# PowerSupply.net
KiCad netlist of a schematic drawn in Altium Designer
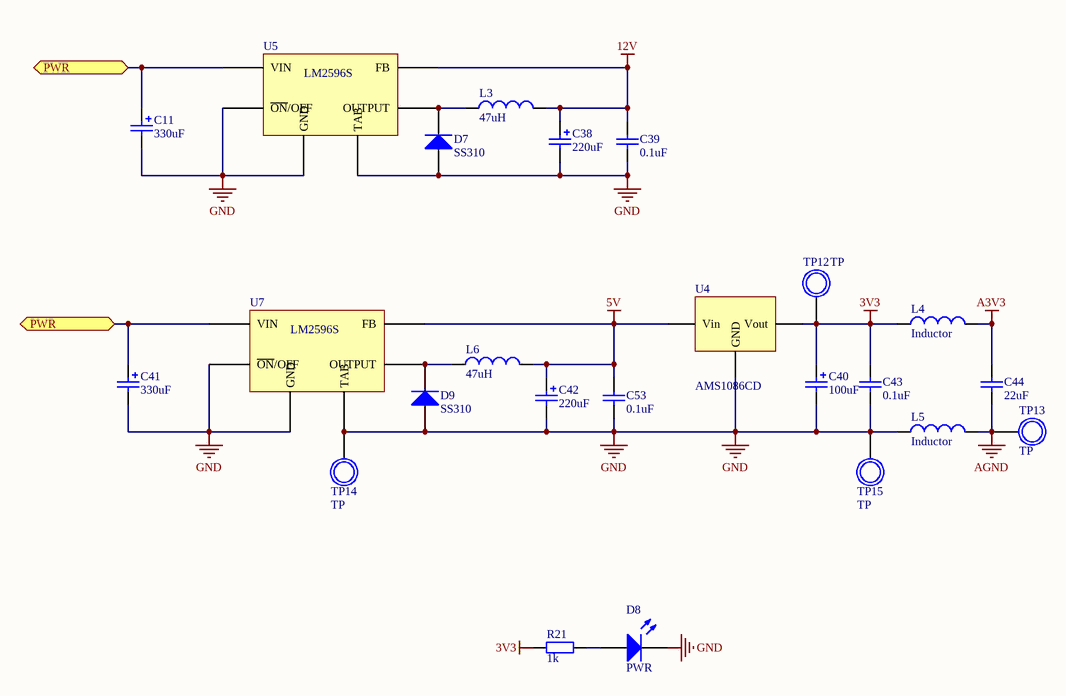
[diagram p0: PowerSupply.SchDoc]

(export (version "E")
  (design (tool "Eeschema 10.0.6"))
  (components
    (comp (ref "C11")
      (value "330uF")
      (footprint "CAPAE109103X105N")
      (description "cap pol")
      (fields (field (name "TOLERANCE") "~{+}- 10%"))
      (libsource (lib "PCB_Project") (part "CAP_Pol"))
    )
    (comp (ref "C38")
      (value "220uF")
      (footprint "CAPAE109103X105N")
      (description "cap pol")
      (fields (field (name "TOLERANCE") "~{+}- 10%"))
      (libsource (lib "PCB_Project") (part "CAP_Pol"))
    )
    (comp (ref "C39")
      (value "0.1uF")
      (footprint "CAP1206")
      (description "CAP NON-POL")
      (fields (field (name "TOLERANCE") "+/-10%"))
      (libsource (lib "PCB_Project") (part "CAP"))
    )
    (comp (ref "C40")
      (value "100uF")
      (footprint "CAPAE109103X105N")
      (description "cap pol")
      (fields (field (name "TOLERANCE") "~{+}- 10%"))
      (libsource (lib "PCB_Project") (part "CAP_Pol"))
    )
    (comp (ref "C41")
      (value "330uF")
      (footprint "CAPAE109103X105N")
      (description "cap pol")
      (fields (field (name "TOLERANCE") "~{+}- 10%"))
      (libsource (lib "PCB_Project") (part "CAP_Pol"))
    )
    (comp (ref "C42")
      (value "220uF")
      (footprint "CAPAE109103X105N")
      (description "cap pol")
      (fields (field (name "TOLERANCE") "~{+}- 10%"))
      (libsource (lib "PCB_Project") (part "CAP_Pol"))
    )
    (comp (ref "C43")
      (value "0.1uF")
      (footprint "CAP0603")
      (description "CAP NON-POL")
      (fields (field (name "TOLERANCE") "+/-10%"))
      (libsource (lib "PCB_Project") (part "CAP"))
    )
    (comp (ref "C44")
      (value "22uF")
      (footprint "CAP1206")
      (description "CAP NON-POL")
      (fields (field (name "TOLERANCE") "+/-10%"))
      (libsource (lib "PCB_Project") (part "CAP"))
    )
    (comp (ref "C53")
      (value "0.1uF")
      (footprint "CAP1206")
      (description "CAP NON-POL")
      (fields (field (name "TOLERANCE") "+/-10%"))
      (libsource (lib "PCB_Project") (part "CAP"))
    )
    (comp (ref "D7")
      (value "SS310")
      (footprint "SMA")
      (description "diode")
      (libsource (lib "PCB_Project") (part "Diode"))
    )
    (comp (ref "D8")
      (value "PWR")
      (footprint "LED0603")
      (description "led")
      (libsource (lib "PCB_Project") (part "LED"))
    )
    (comp (ref "D9")
      (value "SS310")
      (footprint "SMA")
      (description "diode")
      (libsource (lib "PCB_Project") (part "Diode"))
    )
    (comp (ref "L3")
      (value "47uH")
      (footprint "CDRH125")
      (description "Inductor")
      (libsource (lib "PCB_Project") (part "Inductor"))
    )
    (comp (ref "L4")
      (value "Inductor")
      (footprint "IND1206")
      (libsource (lib "PCB_Project") (part "Inductor"))
    )
    (comp (ref "L5")
      (value "Inductor")
      (footprint "IND1206")
      (libsource (lib "PCB_Project") (part "Inductor"))
    )
    (comp (ref "L6")
      (value "47uH")
      (footprint "CDRH125")
      (description "Inductor")
      (libsource (lib "PCB_Project") (part "Inductor"))
    )
    (comp (ref "R21")
      (value "1k")
      (footprint "RES0603")
      (description "res")
      (libsource (lib "PCB_Project") (part "RES"))
    )
    (comp (ref "TP12")
      (value "TP")
      (footprint "PAD85R")
      (description "test point")
      (libsource (lib "PCB_Project") (part "Test_Point"))
    )
    (comp (ref "TP13")
      (value "TP")
      (footprint "PAD85R")
      (description "test point")
      (libsource (lib "PCB_Project") (part "Test_Point"))
    )
    (comp (ref "TP14")
      (value "TP")
      (footprint "PAD85R")
      (description "test point")
      (libsource (lib "PCB_Project") (part "Test_Point"))
    )
    (comp (ref "TP15")
      (value "TP")
      (footprint "PAD85R")
      (description "test point")
      (libsource (lib "PCB_Project") (part "Test_Point"))
    )
    (comp (ref "U4")
      (value "AMS1086CD")
      (footprint "DPAK228P1003X238-3N")
      (description "LDO")
      (libsource (lib "PCB_Project") (part "AMS1086CD"))
    )
    (comp (ref "U5")
      (value "LM2596S")
      (footprint "DPAK170P1435X465-6N")
      (description "1A,52KHz,Step-Down")
      (libsource (lib "PCB_Project") (part "LM2596S"))
    )
    (comp (ref "U7")
      (value "LM2596S")
      (footprint "DPAK170P1435X465-6N")
      (description "1A,52KHz,Step-Down")
      (libsource (lib "PCB_Project") (part "LM2596S"))
    )
  )
  (nets
    (net (code "1") (name "/PWR") (class "Default")
      (node (ref "C11") (pin "2") (pinfunction "2_2") (pintype "passive"))
      (node (ref "C41") (pin "2") (pinfunction "2_2") (pintype "passive"))
      (node (ref "U5") (pin "1") (pinfunction "VIN_1") (pintype "passive"))
      (node (ref "U7") (pin "1") (pinfunction "VIN_1") (pintype "passive"))
    )
    (net (code "2") (name "3V3") (class "Default")
      (node (ref "C40") (pin "2") (pinfunction "2_2") (pintype "passive"))
      (node (ref "C43") (pin "1") (pinfunction "1_1") (pintype "passive"))
      (node (ref "L4") (pin "1") (pinfunction "1_1") (pintype "passive"))
      (node (ref "R21") (pin "1") (pinfunction "1_1") (pintype "passive"))
      (node (ref "TP12") (pin "1") (pinfunction "1_1") (pintype "passive"))
      (node (ref "U4") (pin "2") (pinfunction "Vout_2") (pintype "passive"))
    )
    (net (code "3") (name "5V") (class "Default")
      (node (ref "C42") (pin "2") (pinfunction "2_2") (pintype "passive"))
      (node (ref "C53") (pin "1") (pinfunction "1_1") (pintype "passive"))
      (node (ref "L6") (pin "2") (pinfunction "2_2") (pintype "passive"))
      (node (ref "U4") (pin "3") (pinfunction "Vin_3") (pintype "passive"))
      (node (ref "U7") (pin "4") (pinfunction "FB_4") (pintype "passive"))
    )
    (net (code "4") (name "12V") (class "Default")
      (node (ref "C38") (pin "2") (pinfunction "2_2") (pintype "passive"))
      (node (ref "C39") (pin "1") (pinfunction "1_1") (pintype "passive"))
      (node (ref "L3") (pin "2") (pinfunction "2_2") (pintype "passive"))
      (node (ref "U5") (pin "4") (pinfunction "FB_4") (pintype "passive"))
    )
    (net (code "5") (name "A3V3") (class "Default")
      (node (ref "C44") (pin "1") (pinfunction "1_1") (pintype "passive"))
      (node (ref "L4") (pin "2") (pinfunction "2_2") (pintype "passive"))
    )
    (net (code "6") (name "AGND") (class "Default")
      (node (ref "C44") (pin "2") (pinfunction "2_2") (pintype "passive"))
      (node (ref "L5") (pin "2") (pinfunction "2_2") (pintype "passive"))
      (node (ref "TP13") (pin "1") (pinfunction "1_1") (pintype "passive"))
    )
    (net (code "7") (name "GND") (class "Default")
      (node (ref "C11") (pin "1") (pinfunction "1_1") (pintype "passive"))
      (node (ref "C38") (pin "1") (pinfunction "1_1") (pintype "passive"))
      (node (ref "C39") (pin "2") (pinfunction "2_2") (pintype "passive"))
      (node (ref "C40") (pin "1") (pinfunction "1_1") (pintype "passive"))
      (node (ref "C41") (pin "1") (pinfunction "1_1") (pintype "passive"))
      (node (ref "C42") (pin "1") (pinfunction "1_1") (pintype "passive"))
      (node (ref "C43") (pin "2") (pinfunction "2_2") (pintype "passive"))
      (node (ref "C53") (pin "2") (pinfunction "2_2") (pintype "passive"))
      (node (ref "D7") (pin "1") (pinfunction "A_1") (pintype "passive"))
      (node (ref "D8") (pin "2") (pinfunction "K_2") (pintype "passive"))
      (node (ref "D9") (pin "1") (pinfunction "A_1") (pintype "passive"))
      (node (ref "L5") (pin "1") (pinfunction "1_1") (pintype "passive"))
      (node (ref "TP14") (pin "1") (pinfunction "1_1") (pintype "passive"))
      (node (ref "TP15") (pin "1") (pinfunction "1_1") (pintype "passive"))
      (node (ref "U4") (pin "1") (pinfunction "GND_1") (pintype "passive"))
      (node (ref "U5") (pin "3") (pinfunction "GND_3") (pintype "passive"))
      (node (ref "U5") (pin "5") (pinfunction "~{ON}/OFF_5") (pintype "passive"))
      (node (ref "U5") (pin "6") (pinfunction "TAB_6") (pintype "passive"))
      (node (ref "U7") (pin "3") (pinfunction "GND_3") (pintype "passive"))
      (node (ref "U7") (pin "5") (pinfunction "~{ON}/OFF_5") (pintype "passive"))
      (node (ref "U7") (pin "6") (pinfunction "TAB_6") (pintype "passive"))
    )
    (net (code "8") (name "Net-(D7-K)") (class "Default")
      (node (ref "D7") (pin "2") (pinfunction "K_2") (pintype "passive"))
      (node (ref "L3") (pin "1") (pinfunction "1_1") (pintype "passive"))
      (node (ref "U5") (pin "2") (pinfunction "OUTPUT_2") (pintype "passive"))
    )
    (net (code "9") (name "Net-(D8-A)") (class "Default")
      (node (ref "D8") (pin "1") (pinfunction "A_1") (pintype "passive"))
      (node (ref "R21") (pin "2") (pinfunction "2_2") (pintype "passive"))
    )
    (net (code "10") (name "Net-(D9-K)") (class "Default")
      (node (ref "D9") (pin "2") (pinfunction "K_2") (pintype "passive"))
      (node (ref "L6") (pin "1") (pinfunction "1_1") (pintype "passive"))
      (node (ref "U7") (pin "2") (pinfunction "OUTPUT_2") (pintype "passive"))
    )
  )
)
